# PassiveRelayBoard1_0.net
KiCad netlist of a schematic drawn in EAGLE
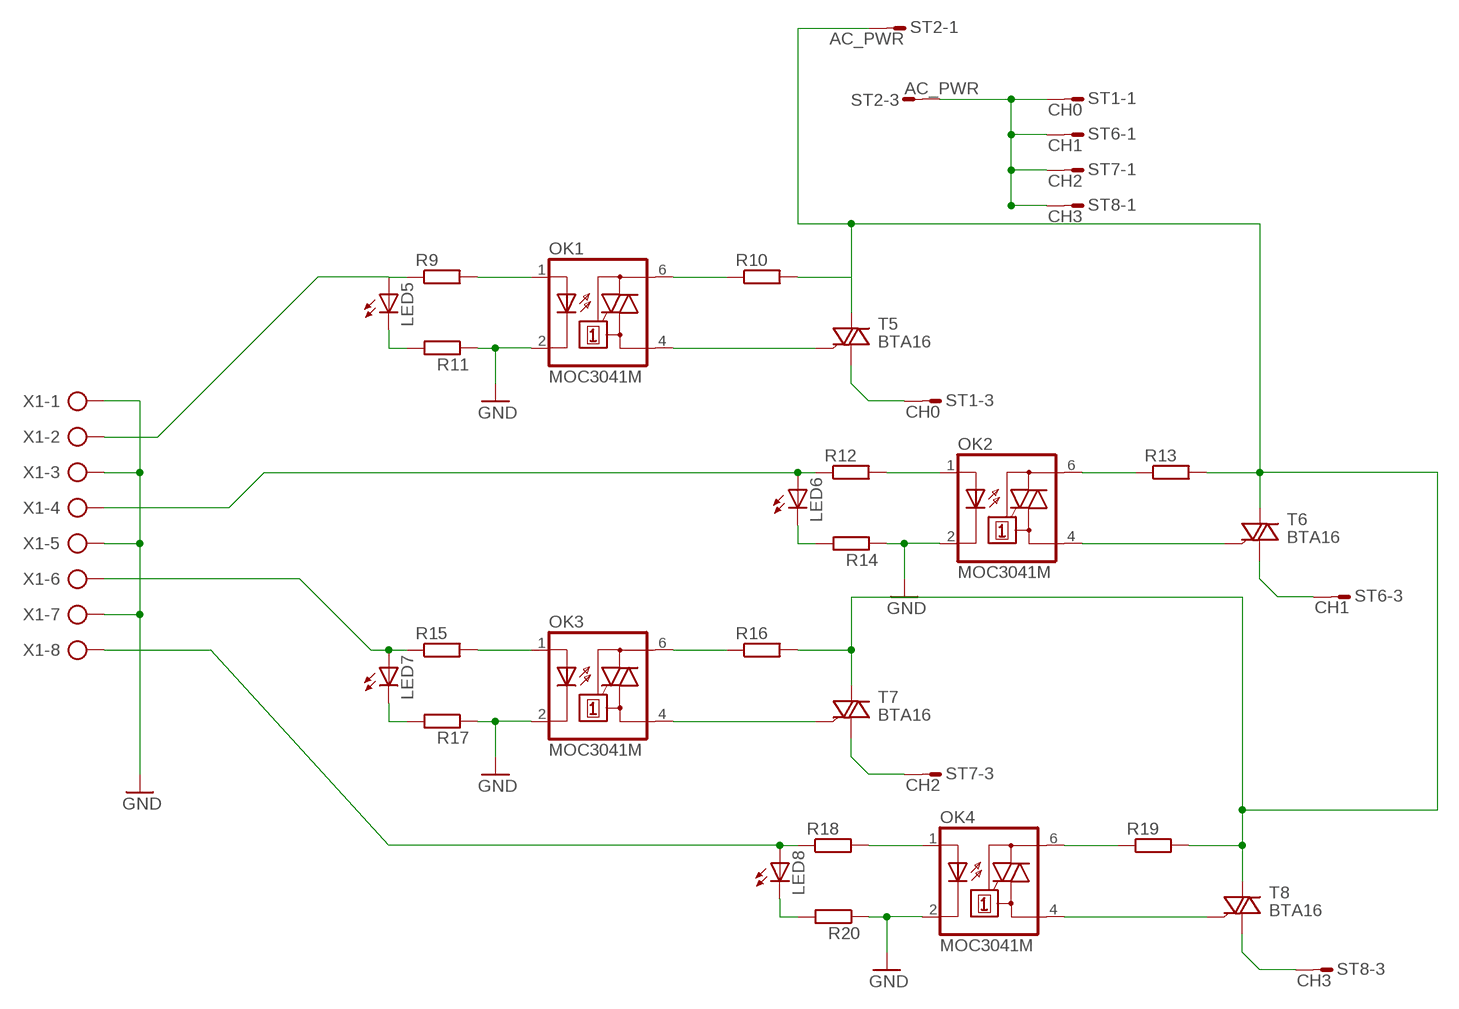
[diagram p0: schematic, sheet 1]

(export (version "E")
  (design (tool "Eeschema 10.0.6"))
  (components
    (comp (ref "LED5")
      (value "LED3MM")
      (footprint "eagle-import:LED3MM")
      (libsource (lib "eagle-import") (part "LED3MM"))
    )
    (comp (ref "LED6")
      (value "LED3MM")
      (footprint "eagle-import:LED3MM")
      (libsource (lib "eagle-import") (part "LED3MM"))
    )
    (comp (ref "LED7")
      (value "LED3MM")
      (footprint "eagle-import:LED3MM")
      (libsource (lib "eagle-import") (part "LED3MM"))
    )
    (comp (ref "LED8")
      (value "LED3MM")
      (footprint "eagle-import:LED3MM")
      (libsource (lib "eagle-import") (part "LED3MM"))
    )
    (comp (ref "OK1")
      (value "MOC3041M")
      (footprint "eagle-import:DIL06")
      (fields (field (name "MF") "FAIRCHILD SEMICONDUCTOR"))
      (libsource (lib "eagle-import") (part "MOC3041M"))
    )
    (comp (ref "OK2")
      (value "MOC3041M")
      (footprint "eagle-import:DIL06")
      (fields (field (name "MF") "FAIRCHILD SEMICONDUCTOR"))
      (libsource (lib "eagle-import") (part "MOC3041M"))
    )
    (comp (ref "OK3")
      (value "MOC3041M")
      (footprint "eagle-import:DIL06")
      (fields (field (name "MF") "FAIRCHILD SEMICONDUCTOR"))
      (libsource (lib "eagle-import") (part "MOC3041M"))
    )
    (comp (ref "OK4")
      (value "MOC3041M")
      (footprint "eagle-import:DIL06")
      (fields (field (name "MF") "FAIRCHILD SEMICONDUCTOR"))
      (libsource (lib "eagle-import") (part "MOC3041M"))
    )
    (comp (ref "R9")
      (value "R-EU_0207/2V")
      (footprint "eagle-import:0207_2V")
      (libsource (lib "eagle-import") (part "R-EU_0207/2V"))
    )
    (comp (ref "R10")
      (value "R-EU_0207/7")
      (footprint "eagle-import:0207_7")
      (libsource (lib "eagle-import") (part "R-EU_0207/7"))
    )
    (comp (ref "R11")
      (value "R-EU_0204/2V")
      (footprint "eagle-import:0204V")
      (libsource (lib "eagle-import") (part "R-EU_0204/2V"))
    )
    (comp (ref "R12")
      (value "R-EU_0207/2V")
      (footprint "eagle-import:0207_2V")
      (libsource (lib "eagle-import") (part "R-EU_0207/2V"))
    )
    (comp (ref "R13")
      (value "R-EU_0207/7")
      (footprint "eagle-import:0207_7")
      (libsource (lib "eagle-import") (part "R-EU_0207/7"))
    )
    (comp (ref "R14")
      (value "R-EU_0204/2V")
      (footprint "eagle-import:0204V")
      (libsource (lib "eagle-import") (part "R-EU_0204/2V"))
    )
    (comp (ref "R15")
      (value "R-EU_0207/2V")
      (footprint "eagle-import:0207_2V")
      (libsource (lib "eagle-import") (part "R-EU_0207/2V"))
    )
    (comp (ref "R16")
      (value "R-EU_0207/7")
      (footprint "eagle-import:0207_7")
      (libsource (lib "eagle-import") (part "R-EU_0207/7"))
    )
    (comp (ref "R17")
      (value "R-EU_0204/2V")
      (footprint "eagle-import:0204V")
      (libsource (lib "eagle-import") (part "R-EU_0204/2V"))
    )
    (comp (ref "R18")
      (value "R-EU_0207/2V")
      (footprint "eagle-import:0207_2V")
      (libsource (lib "eagle-import") (part "R-EU_0207/2V"))
    )
    (comp (ref "R19")
      (value "R-EU_0207/7")
      (footprint "eagle-import:0207_7")
      (libsource (lib "eagle-import") (part "R-EU_0207/7"))
    )
    (comp (ref "R20")
      (value "R-EU_0204/2V")
      (footprint "eagle-import:0204V")
      (libsource (lib "eagle-import") (part "R-EU_0204/2V"))
    )
    (comp (ref "ST1")
      (value "CH0")
      (footprint "eagle-import:MSF3")
      (libsource (lib "eagle-import") (part "MSF3"))
    )
    (comp (ref "ST2")
      (value "AC_PWR")
      (footprint "eagle-import:MSF3")
      (libsource (lib "eagle-import") (part "MSF3"))
    )
    (comp (ref "ST6")
      (value "CH1")
      (footprint "eagle-import:MSF3")
      (libsource (lib "eagle-import") (part "MSF3"))
    )
    (comp (ref "ST7")
      (value "CH2")
      (footprint "eagle-import:MSF3")
      (libsource (lib "eagle-import") (part "MSF3"))
    )
    (comp (ref "ST8")
      (value "CH3")
      (footprint "eagle-import:MSF3")
      (libsource (lib "eagle-import") (part "MSF3"))
    )
    (comp (ref "T5")
      (value "BTA16")
      (footprint "eagle-import:TO220BV")
      (libsource (lib "eagle-import") (part "BT138-V"))
    )
    (comp (ref "T6")
      (value "BTA16")
      (footprint "eagle-import:TO220BV")
      (libsource (lib "eagle-import") (part "BT138-V"))
    )
    (comp (ref "T7")
      (value "BTA16")
      (footprint "eagle-import:TO220BV")
      (libsource (lib "eagle-import") (part "BT138-V"))
    )
    (comp (ref "T8")
      (value "BTA16")
      (footprint "eagle-import:TO220BV")
      (libsource (lib "eagle-import") (part "BT138-V"))
    )
    (comp (ref "X1")
      (value "AK300/8")
      (footprint "eagle-import:AK300_8")
      (libsource (lib "eagle-import") (part "AK300/8"))
    )
  )
  (nets
    (net (code "1") (name "GND") (class "Default")
      (node (ref "OK1") (pin "2") (pinfunction "C_2") (pintype "passive"))
      (node (ref "OK2") (pin "2") (pinfunction "C_2") (pintype "passive"))
      (node (ref "OK3") (pin "2") (pinfunction "C_2") (pintype "passive"))
      (node (ref "OK4") (pin "2") (pinfunction "C_2") (pintype "passive"))
      (node (ref "R11") (pin "1") (pinfunction "1_1") (pintype "passive"))
      (node (ref "R14") (pin "1") (pinfunction "1_1") (pintype "passive"))
      (node (ref "R17") (pin "1") (pinfunction "1_1") (pintype "passive"))
      (node (ref "R20") (pin "1") (pinfunction "1_1") (pintype "passive"))
      (node (ref "X1") (pin "1") (pinfunction "KL_1") (pintype "passive"))
      (node (ref "X1") (pin "3") (pinfunction "KL_3") (pintype "passive"))
      (node (ref "X1") (pin "5") (pinfunction "KL_5") (pintype "passive"))
      (node (ref "X1") (pin "7") (pinfunction "KL_7") (pintype "passive"))
    )
    (net (code "2") (name "Net-(LED5-C)") (class "Default")
      (node (ref "LED5") (pin "K") (pinfunction "C_K") (pintype "passive"))
      (node (ref "R11") (pin "2") (pinfunction "2_2") (pintype "passive"))
    )
    (net (code "3") (name "Net-(LED6-C)") (class "Default")
      (node (ref "LED6") (pin "K") (pinfunction "C_K") (pintype "passive"))
      (node (ref "R14") (pin "2") (pinfunction "2_2") (pintype "passive"))
    )
    (net (code "4") (name "Net-(LED7-C)") (class "Default")
      (node (ref "LED7") (pin "K") (pinfunction "C_K") (pintype "passive"))
      (node (ref "R17") (pin "2") (pinfunction "2_2") (pintype "passive"))
    )
    (net (code "5") (name "Net-(LED8-C)") (class "Default")
      (node (ref "LED8") (pin "K") (pinfunction "C_K") (pintype "passive"))
      (node (ref "R20") (pin "2") (pinfunction "2_2") (pintype "passive"))
    )
    (net (code "6") (name "Net-(OK1-A)") (class "Default")
      (node (ref "OK1") (pin "1") (pinfunction "A_1") (pintype "passive"))
      (node (ref "R9") (pin "2") (pinfunction "2_2") (pintype "passive"))
    )
    (net (code "7") (name "Net-(OK1-A1)") (class "Default")
      (node (ref "OK1") (pin "4") (pinfunction "A1_4") (pintype "passive"))
      (node (ref "T5") (pin "G") (pinfunction "G_G") (pintype "passive"))
    )
    (net (code "8") (name "Net-(OK1-A2)") (class "Default")
      (node (ref "OK1") (pin "6") (pinfunction "A2_6") (pintype "passive"))
      (node (ref "R10") (pin "1") (pinfunction "1_1") (pintype "passive"))
    )
    (net (code "9") (name "Net-(OK2-A)") (class "Default")
      (node (ref "OK2") (pin "1") (pinfunction "A_1") (pintype "passive"))
      (node (ref "R12") (pin "2") (pinfunction "2_2") (pintype "passive"))
    )
    (net (code "10") (name "Net-(OK2-A1)") (class "Default")
      (node (ref "OK2") (pin "4") (pinfunction "A1_4") (pintype "passive"))
      (node (ref "T6") (pin "G") (pinfunction "G_G") (pintype "passive"))
    )
    (net (code "11") (name "Net-(OK2-A2)") (class "Default")
      (node (ref "OK2") (pin "6") (pinfunction "A2_6") (pintype "passive"))
      (node (ref "R13") (pin "1") (pinfunction "1_1") (pintype "passive"))
    )
    (net (code "12") (name "Net-(OK3-A)") (class "Default")
      (node (ref "OK3") (pin "1") (pinfunction "A_1") (pintype "passive"))
      (node (ref "R15") (pin "2") (pinfunction "2_2") (pintype "passive"))
    )
    (net (code "13") (name "Net-(OK3-A1)") (class "Default")
      (node (ref "OK3") (pin "4") (pinfunction "A1_4") (pintype "passive"))
      (node (ref "T7") (pin "G") (pinfunction "G_G") (pintype "passive"))
    )
    (net (code "14") (name "Net-(OK3-A2)") (class "Default")
      (node (ref "OK3") (pin "6") (pinfunction "A2_6") (pintype "passive"))
      (node (ref "R16") (pin "1") (pinfunction "1_1") (pintype "passive"))
    )
    (net (code "15") (name "Net-(OK4-A)") (class "Default")
      (node (ref "OK4") (pin "1") (pinfunction "A_1") (pintype "passive"))
      (node (ref "R18") (pin "2") (pinfunction "2_2") (pintype "passive"))
    )
    (net (code "16") (name "Net-(OK4-A1)") (class "Default")
      (node (ref "OK4") (pin "4") (pinfunction "A1_4") (pintype "passive"))
      (node (ref "T8") (pin "G") (pinfunction "G_G") (pintype "passive"))
    )
    (net (code "17") (name "Net-(OK4-A2)") (class "Default")
      (node (ref "OK4") (pin "6") (pinfunction "A2_6") (pintype "passive"))
      (node (ref "R19") (pin "1") (pinfunction "1_1") (pintype "passive"))
    )
    (net (code "18") (name "Net-(ST1A-S)") (class "Default")
      (node (ref "ST1") (pin "1") (pinfunction "S_1") (pintype "passive"))
      (node (ref "ST2") (pin "3") (pinfunction "S_3") (pintype "passive"))
      (node (ref "ST6") (pin "1") (pinfunction "S_1") (pintype "passive"))
      (node (ref "ST7") (pin "1") (pinfunction "S_1") (pintype "passive"))
      (node (ref "ST8") (pin "1") (pinfunction "S_1") (pintype "passive"))
    )
    (net (code "19") (name "Net-(ST1C-S)") (class "Default")
      (node (ref "ST1") (pin "3") (pinfunction "S_3") (pintype "passive"))
      (node (ref "T5") (pin "T1") (pinfunction "A1_T1") (pintype "passive"))
    )
    (net (code "20") (name "Net-(ST2A-S)") (class "Default")
      (node (ref "R10") (pin "2") (pinfunction "2_2") (pintype "passive"))
      (node (ref "R13") (pin "2") (pinfunction "2_2") (pintype "passive"))
      (node (ref "R16") (pin "2") (pinfunction "2_2") (pintype "passive"))
      (node (ref "R19") (pin "2") (pinfunction "2_2") (pintype "passive"))
      (node (ref "ST2") (pin "1") (pinfunction "S_1") (pintype "passive"))
      (node (ref "T5") (pin "T2") (pinfunction "A2_T2") (pintype "passive"))
      (node (ref "T6") (pin "T2") (pinfunction "A2_T2") (pintype "passive"))
      (node (ref "T7") (pin "T2") (pinfunction "A2_T2") (pintype "passive"))
      (node (ref "T8") (pin "T2") (pinfunction "A2_T2") (pintype "passive"))
    )
    (net (code "21") (name "Net-(ST6C-S)") (class "Default")
      (node (ref "ST6") (pin "3") (pinfunction "S_3") (pintype "passive"))
      (node (ref "T6") (pin "T1") (pinfunction "A1_T1") (pintype "passive"))
    )
    (net (code "22") (name "Net-(ST7C-S)") (class "Default")
      (node (ref "ST7") (pin "3") (pinfunction "S_3") (pintype "passive"))
      (node (ref "T7") (pin "T1") (pinfunction "A1_T1") (pintype "passive"))
    )
    (net (code "23") (name "Net-(ST8C-S)") (class "Default")
      (node (ref "ST8") (pin "3") (pinfunction "S_3") (pintype "passive"))
      (node (ref "T8") (pin "T1") (pinfunction "A1_T1") (pintype "passive"))
    )
    (net (code "24") (name "Net-(X1B-KL)") (class "Default")
      (node (ref "LED5") (pin "A") (pinfunction "A_A") (pintype "passive"))
      (node (ref "R9") (pin "1") (pinfunction "1_1") (pintype "passive"))
      (node (ref "X1") (pin "2") (pinfunction "KL_2") (pintype "passive"))
    )
    (net (code "25") (name "Net-(X1D-KL)") (class "Default")
      (node (ref "LED6") (pin "A") (pinfunction "A_A") (pintype "passive"))
      (node (ref "R12") (pin "1") (pinfunction "1_1") (pintype "passive"))
      (node (ref "X1") (pin "4") (pinfunction "KL_4") (pintype "passive"))
    )
    (net (code "26") (name "Net-(X1F-KL)") (class "Default")
      (node (ref "LED7") (pin "A") (pinfunction "A_A") (pintype "passive"))
      (node (ref "R15") (pin "1") (pinfunction "1_1") (pintype "passive"))
      (node (ref "X1") (pin "6") (pinfunction "KL_6") (pintype "passive"))
    )
    (net (code "27") (name "Net-(X1H-KL)") (class "Default")
      (node (ref "LED8") (pin "A") (pinfunction "A_A") (pintype "passive"))
      (node (ref "R18") (pin "1") (pinfunction "1_1") (pintype "passive"))
      (node (ref "X1") (pin "8") (pinfunction "KL_8") (pintype "passive"))
    )
  )
)
